# voltage_regulator.net
KiCad netlist of a schematic drawn in Altium Designer
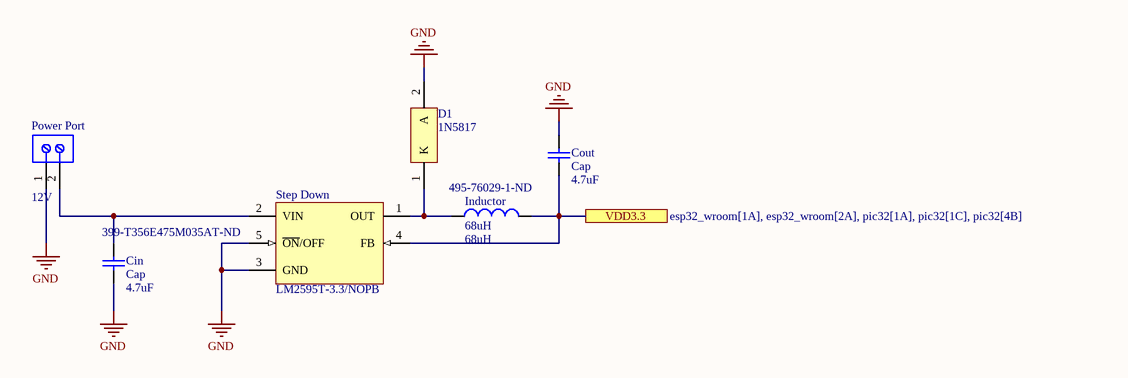
[diagram p0: voltage_regulator.SchDoc]

(export (version "E")
  (design (tool "Eeschema 10.0.6"))
  (components
    (comp (ref "Cin")
      (value "Cap")
      (footprint "RAD-0.3")
      (description "Capacitor")
      (fields
        (field (name "ALTIUM_VALUE") "4.7uF")
        (field (name "SUPPLIER PART NUMBER 1") "399-T356E475M035AT-ND")
        (field (name "PUBLISHER") "Altium Limited")
      )
      (libsource (lib "Miscellaneous Devices") (part "Cap"))
    )
    (comp (ref "Cout")
      (value "Cap")
      (footprint "RAD-0.3")
      (description "Capacitor")
      (fields (field (name "ALTIUM_VALUE") "4.7uF") (field (name "PUBLISHER") "Altium Limited"))
      (libsource (lib "Miscellaneous Devices") (part "Cap"))
    )
    (comp (ref "D1")
      (value "1N5817")
      (footprint "ONSC-AXIAL_LEAD-2-59-10_P")
      (description "Rectifier, 2-Pin Axial_Lead, Pb-Free, Bulk Bag")
      (fields (field (name "MANUFACTURER") "On Semiconductor"))
      (libsource (lib "Altium Content Vault") (part "ONSC-D-K1A2-2_A"))
    )
    (comp (ref "Inductor")
      (value "68uH")
      (footprint "0402-A")
      (description "Inductor")
      (fields
        (field (name "ALTIUM_VALUE") "68uH")
        (field (name "SUPPLIER PART NUMBER 1") "495-76029-1-ND")
        (field (name "PUBLISHER") "Altium Limited")
      )
      (libsource (lib "Miscellaneous Devices") (part "Inductor"))
    )
    (comp (ref "Power Port")
      (value "12V")
      (footprint "691102710002")
      (description "Series 102 - 5.00 mm Horizontal Entry Modular with Pressure Clamp WR-TBL, 2 pin\r\n691102710002")
      (fields
        (field (name "MANUFACTURER") "Wurth Elektronik")
        (field (name "PART NUMBER") "691102710002")
        (field (name "PUBLISHER") "WurthElektronik")
      )
      (libsource (lib "Altium Content Vault") (part "WE-CN-1P-F-TB2"))
    )
    (comp (ref "Step Down")
      (value "LM2595T-3.3/NOPB")
      (footprint "NDH0005A")
      (description "SIMPLE SWITCHER® Power Converter 150 KHz 1A Step-Down Voltage Regulator, 5-pin TO-220, Pb-Free")
      (fields (field (name "MANUFACTURER") "Texas Instruments"))
      (libsource (lib "Altium Content Vault") (part "PM-REG-LM2595T-12"))
    )
  )
  (nets
    (net (code "1") (name "/VDD3.3") (class "Default")
      (node (ref "Cout") (pin "1") (pinfunction "1_1") (pintype "passive"))
      (node (ref "Inductor") (pin "2") (pinfunction "2_2") (pintype "passive"))
      (node (ref "Step Down") (pin "4") (pinfunction "FB_4") (pintype "input"))
    )
    (net (code "2") (name "GND") (class "Default")
      (node (ref "Cin") (pin "1") (pinfunction "1_1") (pintype "passive"))
      (node (ref "Cout") (pin "2") (pinfunction "2_2") (pintype "passive"))
      (node (ref "D1") (pin "2") (pinfunction "A_2") (pintype "passive"))
      (node (ref "Power Port") (pin "1") (pinfunction "1_1") (pintype "passive"))
      (node (ref "Step Down") (pin "3") (pinfunction "GND_3") (pintype "power_in"))
      (node (ref "Step Down") (pin "5") (pinfunction "~{ON}/OFF_5") (pintype "input"))
    )
    (net (code "3") (name "Net-(D1-K)") (class "Default")
      (node (ref "D1") (pin "1") (pinfunction "K_1") (pintype "passive"))
      (node (ref "Inductor") (pin "1") (pinfunction "1_1") (pintype "passive"))
      (node (ref "Step Down") (pin "1") (pinfunction "OUT_1") (pintype "power_in"))
    )
    (net (code "4") (name "Net-(Step Down-VIN)") (class "Default")
      (node (ref "Cin") (pin "2") (pinfunction "2_2") (pintype "passive"))
      (node (ref "Power Port") (pin "2") (pinfunction "2_2") (pintype "passive"))
      (node (ref "Step Down") (pin "2") (pinfunction "VIN_2") (pintype "power_in"))
    )
  )
)
